# SparkFunVKeyVoltageKeypad.net
KiCad netlist of a schematic drawn in EAGLE
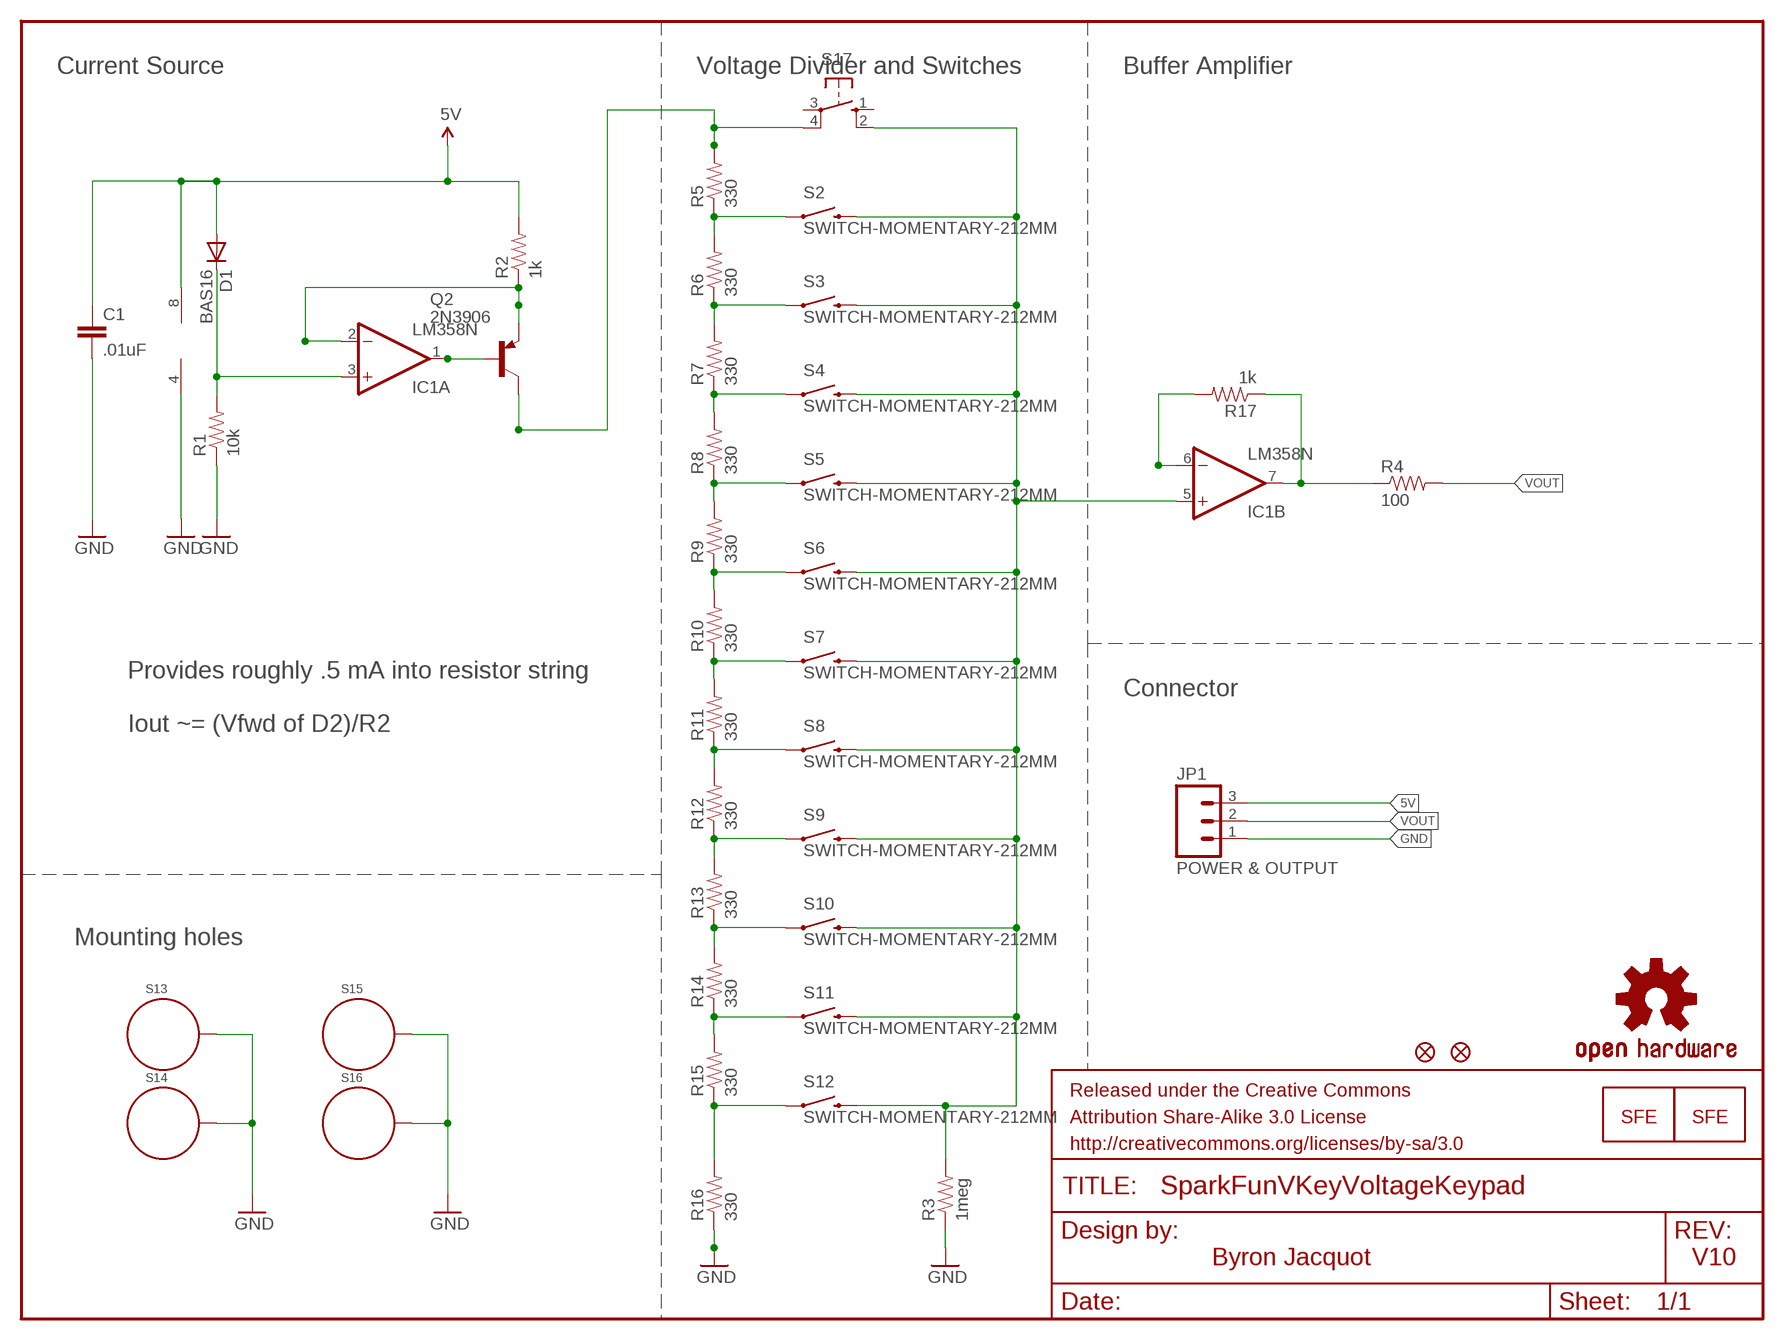
[diagram p0: schematic, sheet 1]

(export (version "E")
  (design (tool "Eeschema 10.0.6"))
  (components
    (comp (ref "C1")
      (value ".01uF")
      (footprint "eagle-import:0603-CAP")
      (libsource (lib "eagle-import") (part "10NF/10000PF-50V-10%(0603)"))
    )
    (comp (ref "D1")
      (value "BAS16")
      (footprint "eagle-import:SOD-323")
      (libsource (lib "eagle-import") (part "DIODESOD"))
    )
    (comp (ref "FID1")
      (value "FIDUCIALUFIDUCIAL")
      (footprint "eagle-import:MICRO-FIDUCIAL")
      (libsource (lib "eagle-import") (part "FIDUCIALUFIDUCIAL"))
    )
    (comp (ref "FID2")
      (value "FIDUCIALUFIDUCIAL")
      (footprint "eagle-import:MICRO-FIDUCIAL")
      (libsource (lib "eagle-import") (part "FIDUCIALUFIDUCIAL"))
    )
    (comp (ref "FRAME1")
      (value "FRAME-LETTER")
      (footprint "eagle-import:CREATIVE_COMMONS")
      (libsource (lib "eagle-import") (part "FRAME-LETTER"))
    )
    (comp (ref "IC1")
      (value "LM358N")
      (footprint "eagle-import:DIL08")
      (libsource (lib "eagle-import") (part "LM358N"))
    )
    (comp (ref "JP1")
      (value "POWER & OUTPUT")
      (footprint "eagle-import:1X03_NO_SILK")
      (libsource (lib "eagle-import") (part "M031X03_NO_SILK"))
    )
    (comp (ref "LOGO1")
      (value "LOGO-SFENEW")
      (footprint "eagle-import:SFE-NEW-WEBLOGO")
      (libsource (lib "eagle-import") (part "LOGO-SFENEW"))
    )
    (comp (ref "LOGO2")
      (value "LOGO-SFENEW")
      (footprint "eagle-import:SFE-NEW-WEBLOGO")
      (libsource (lib "eagle-import") (part "LOGO-SFENEW"))
    )
    (comp (ref "LOGO3")
      (value "OSHW-LOGOM")
      (footprint "eagle-import:OSHW-LOGO-M")
      (libsource (lib "eagle-import") (part "OSHW-LOGOM"))
    )
    (comp (ref "LOGO4")
      (value "OSHW-LOGOL")
      (footprint "eagle-import:OSHW-LOGO-L")
      (libsource (lib "eagle-import") (part "OSHW-LOGOL"))
    )
    (comp (ref "Q2")
      (value "2N3906")
      (footprint "eagle-import:TO92")
      (libsource (lib "eagle-import") (part "2N3906"))
    )
    (comp (ref "R1")
      (value "10k")
      (footprint "eagle-import:0603-RES")
      (libsource (lib "eagle-import") (part "10KOHM1/10W1%(0603)0603"))
    )
    (comp (ref "R2")
      (value "1k")
      (footprint "eagle-import:0603-RES")
      (libsource (lib "eagle-import") (part "1KOHM1/10W1%(0603)"))
    )
    (comp (ref "R3")
      (value "1meg")
      (footprint "eagle-import:0603-RES")
      (libsource (lib "eagle-import") (part "1M-1%"))
    )
    (comp (ref "R4")
      (value "100")
      (footprint "eagle-import:0603-RES")
      (libsource (lib "eagle-import") (part "100OHM1/10W1%(0603)"))
    )
    (comp (ref "R5")
      (value "330")
      (footprint "eagle-import:0603-RES")
      (libsource (lib "eagle-import") (part "330OHM1/10W1%(0603)"))
    )
    (comp (ref "R6")
      (value "330")
      (footprint "eagle-import:0603-RES")
      (fields (field (name "PROD_ID") "RES-00818"))
      (libsource (lib "eagle-import") (part "330OHM1/10W1%(0603)"))
    )
    (comp (ref "R7")
      (value "330")
      (footprint "eagle-import:0603-RES")
      (fields (field (name "PROD_ID") "RES-00818"))
      (libsource (lib "eagle-import") (part "330OHM1/10W1%(0603)"))
    )
    (comp (ref "R8")
      (value "330")
      (footprint "eagle-import:0603-RES")
      (fields (field (name "PROD_ID") "RES-00818"))
      (libsource (lib "eagle-import") (part "330OHM1/10W1%(0603)"))
    )
    (comp (ref "R9")
      (value "330")
      (footprint "eagle-import:0603-RES")
      (fields (field (name "PROD_ID") "RES-00818"))
      (libsource (lib "eagle-import") (part "330OHM1/10W1%(0603)"))
    )
    (comp (ref "R10")
      (value "330")
      (footprint "eagle-import:0603-RES")
      (fields (field (name "PROD_ID") "RES-00818"))
      (libsource (lib "eagle-import") (part "330OHM1/10W1%(0603)"))
    )
    (comp (ref "R11")
      (value "330")
      (footprint "eagle-import:0603-RES")
      (fields (field (name "PROD_ID") "RES-00818"))
      (libsource (lib "eagle-import") (part "330OHM1/10W1%(0603)"))
    )
    (comp (ref "R12")
      (value "330")
      (footprint "eagle-import:0603-RES")
      (fields (field (name "PROD_ID") "RES-00818"))
      (libsource (lib "eagle-import") (part "330OHM1/10W1%(0603)"))
    )
    (comp (ref "R13")
      (value "330")
      (footprint "eagle-import:0603-RES")
      (fields (field (name "PROD_ID") "RES-00818"))
      (libsource (lib "eagle-import") (part "330OHM1/10W1%(0603)"))
    )
    (comp (ref "R14")
      (value "330")
      (footprint "eagle-import:0603-RES")
      (fields (field (name "PROD_ID") "RES-00818"))
      (libsource (lib "eagle-import") (part "330OHM1/10W1%(0603)"))
    )
    (comp (ref "R15")
      (value "330")
      (footprint "eagle-import:0603-RES")
      (fields (field (name "PROD_ID") "RES-00818"))
      (libsource (lib "eagle-import") (part "330OHM1/10W1%(0603)"))
    )
    (comp (ref "R16")
      (value "330")
      (footprint "eagle-import:0603-RES")
      (fields (field (name "PROD_ID") "RES-00818"))
      (libsource (lib "eagle-import") (part "330OHM1/10W1%(0603)"))
    )
    (comp (ref "R17")
      (value "1k")
      (footprint "eagle-import:0603-RES")
      (libsource (lib "eagle-import") (part "1KOHM1/10W1%(0603)"))
    )
    (comp (ref "S2")
      (value "SWITCH-MOMENTARY-212MM")
      (footprint "eagle-import:TACTILE-PTH-12MM")
      (libsource (lib "eagle-import") (part "SWITCH-MOMENTARY-212MM"))
    )
    (comp (ref "S3")
      (value "SWITCH-MOMENTARY-212MM")
      (footprint "eagle-import:TACTILE-PTH-12MM")
      (libsource (lib "eagle-import") (part "SWITCH-MOMENTARY-212MM"))
    )
    (comp (ref "S4")
      (value "SWITCH-MOMENTARY-212MM")
      (footprint "eagle-import:TACTILE-PTH-12MM")
      (libsource (lib "eagle-import") (part "SWITCH-MOMENTARY-212MM"))
    )
    (comp (ref "S5")
      (value "SWITCH-MOMENTARY-212MM")
      (footprint "eagle-import:TACTILE-PTH-12MM")
      (libsource (lib "eagle-import") (part "SWITCH-MOMENTARY-212MM"))
    )
    (comp (ref "S6")
      (value "SWITCH-MOMENTARY-212MM")
      (footprint "eagle-import:TACTILE-PTH-12MM")
      (libsource (lib "eagle-import") (part "SWITCH-MOMENTARY-212MM"))
    )
    (comp (ref "S7")
      (value "SWITCH-MOMENTARY-212MM")
      (footprint "eagle-import:TACTILE-PTH-12MM")
      (libsource (lib "eagle-import") (part "SWITCH-MOMENTARY-212MM"))
    )
    (comp (ref "S8")
      (value "SWITCH-MOMENTARY-212MM")
      (footprint "eagle-import:TACTILE-PTH-12MM")
      (libsource (lib "eagle-import") (part "SWITCH-MOMENTARY-212MM"))
    )
    (comp (ref "S9")
      (value "SWITCH-MOMENTARY-212MM")
      (footprint "eagle-import:TACTILE-PTH-12MM")
      (libsource (lib "eagle-import") (part "SWITCH-MOMENTARY-212MM"))
    )
    (comp (ref "S10")
      (value "SWITCH-MOMENTARY-212MM")
      (footprint "eagle-import:TACTILE-PTH-12MM")
      (libsource (lib "eagle-import") (part "SWITCH-MOMENTARY-212MM"))
    )
    (comp (ref "S11")
      (value "SWITCH-MOMENTARY-212MM")
      (footprint "eagle-import:TACTILE-PTH-12MM")
      (libsource (lib "eagle-import") (part "SWITCH-MOMENTARY-212MM"))
    )
    (comp (ref "S12")
      (value "SWITCH-MOMENTARY-212MM")
      (footprint "eagle-import:TACTILE-PTH-12MM")
      (libsource (lib "eagle-import") (part "SWITCH-MOMENTARY-212MM"))
    )
    (comp (ref "S13")
      (value "STANDOFF_ELECTRICAL")
      (footprint "eagle-import:STANDOFF-ELECTRICAL")
      (libsource (lib "eagle-import") (part "STANDOFF_ELECTRICAL"))
    )
    (comp (ref "S14")
      (value "STANDOFF_ELECTRICAL")
      (footprint "eagle-import:STANDOFF-ELECTRICAL")
      (libsource (lib "eagle-import") (part "STANDOFF_ELECTRICAL"))
    )
    (comp (ref "S15")
      (value "STANDOFF_ELECTRICAL")
      (footprint "eagle-import:STANDOFF-ELECTRICAL")
      (libsource (lib "eagle-import") (part "STANDOFF_ELECTRICAL"))
    )
    (comp (ref "S16")
      (value "STANDOFF_ELECTRICAL")
      (footprint "eagle-import:STANDOFF-ELECTRICAL")
      (libsource (lib "eagle-import") (part "STANDOFF_ELECTRICAL"))
    )
    (comp (ref "S17")
      (value "10-XX")
      (footprint "eagle-import:B3F-10XX")
      (fields (field (name "MPN") "B3F-1000"))
      (libsource (lib "eagle-import") (part "10-XX"))
    )
  )
  (nets
    (net (code "1") (name "5V") (class "Default")
      (node (ref "C1") (pin "1") (pinfunction "1_1") (pintype "passive"))
      (node (ref "D1") (pin "2") (pinfunction "A_2") (pintype "passive"))
      (node (ref "IC1") (pin "8") (pinfunction "V+_8") (pintype "power_in"))
      (node (ref "JP1") (pin "3") (pinfunction "3_3") (pintype "passive"))
      (node (ref "R2") (pin "2") (pinfunction "2_2") (pintype "passive"))
    )
    (net (code "2") (name "GND") (class "Default")
      (node (ref "C1") (pin "2") (pinfunction "2_2") (pintype "passive"))
      (node (ref "IC1") (pin "4") (pinfunction "V-_4") (pintype "power_in"))
      (node (ref "JP1") (pin "1") (pinfunction "1_1") (pintype "passive"))
      (node (ref "R1") (pin "1") (pinfunction "1_1") (pintype "passive"))
      (node (ref "R16") (pin "1") (pinfunction "1_1") (pintype "passive"))
      (node (ref "R3") (pin "1") (pinfunction "1_1") (pintype "passive"))
      (node (ref "S13") (pin "P1") (pinfunction "P$1_P1") (pintype "bidirectional"))
      (node (ref "S14") (pin "P1") (pinfunction "P$1_P1") (pintype "bidirectional"))
      (node (ref "S15") (pin "P1") (pinfunction "P$1_P1") (pintype "bidirectional"))
      (node (ref "S16") (pin "P1") (pinfunction "P$1_P1") (pintype "bidirectional"))
    )
    (net (code "3") (name "Net-(D1-C)") (class "Default")
      (node (ref "D1") (pin "1") (pinfunction "C_1") (pintype "passive"))
      (node (ref "IC1") (pin "3") (pinfunction "+IN_3") (pintype "input"))
      (node (ref "R1") (pin "2") (pinfunction "2_2") (pintype "passive"))
    )
    (net (code "4") (name "Net-(IC1A--IN)") (class "Default")
      (node (ref "IC1") (pin "2") (pinfunction "-IN_2") (pintype "input"))
      (node (ref "Q2") (pin "3") (pinfunction "E_3") (pintype "passive"))
      (node (ref "R2") (pin "1") (pinfunction "1_1") (pintype "passive"))
    )
    (net (code "5") (name "Net-(IC1A-OUT)") (class "Default")
      (node (ref "IC1") (pin "1") (pinfunction "OUT_1") (pintype "output"))
      (node (ref "Q2") (pin "2") (pinfunction "B_2") (pintype "passive"))
    )
    (net (code "6") (name "Net-(IC1B-+IN)") (class "Default")
      (node (ref "IC1") (pin "5") (pinfunction "+IN_5") (pintype "input"))
      (node (ref "R3") (pin "2") (pinfunction "2_2") (pintype "passive"))
      (node (ref "S10") (pin "3") (pinfunction "2_3") (pintype "passive"))
      (node (ref "S11") (pin "3") (pinfunction "2_3") (pintype "passive"))
      (node (ref "S12") (pin "3") (pinfunction "2_3") (pintype "passive"))
      (node (ref "S17") (pin "2") (pinfunction "S1_2") (pintype "passive"))
      (node (ref "S2") (pin "3") (pinfunction "2_3") (pintype "passive"))
      (node (ref "S3") (pin "3") (pinfunction "2_3") (pintype "passive"))
      (node (ref "S4") (pin "3") (pinfunction "2_3") (pintype "passive"))
      (node (ref "S5") (pin "3") (pinfunction "2_3") (pintype "passive"))
      (node (ref "S6") (pin "3") (pinfunction "2_3") (pintype "passive"))
      (node (ref "S7") (pin "3") (pinfunction "2_3") (pintype "passive"))
      (node (ref "S8") (pin "3") (pinfunction "2_3") (pintype "passive"))
      (node (ref "S9") (pin "3") (pinfunction "2_3") (pintype "passive"))
    )
    (net (code "7") (name "Net-(IC1B--IN)") (class "Default")
      (node (ref "IC1") (pin "6") (pinfunction "-IN_6") (pintype "input"))
      (node (ref "R17") (pin "2") (pinfunction "2_2") (pintype "passive"))
    )
    (net (code "8") (name "Net-(IC1B-OUT)") (class "Default")
      (node (ref "IC1") (pin "7") (pinfunction "OUT_7") (pintype "output"))
      (node (ref "R17") (pin "1") (pinfunction "1_1") (pintype "passive"))
      (node (ref "R4") (pin "1") (pinfunction "1_1") (pintype "passive"))
    )
    (net (code "9") (name "Net-(Q2-C)") (class "Default")
      (node (ref "Q2") (pin "1") (pinfunction "C_1") (pintype "passive"))
      (node (ref "R5") (pin "2") (pinfunction "2_2") (pintype "passive"))
      (node (ref "S17") (pin "4") (pinfunction "P1_4") (pintype "passive"))
    )
    (net (code "10") (name "Net-(R5-Pad1)") (class "Default")
      (node (ref "R5") (pin "1") (pinfunction "1_1") (pintype "passive"))
      (node (ref "R6") (pin "2") (pinfunction "2_2") (pintype "passive"))
      (node (ref "S2") (pin "1") (pinfunction "1_1") (pintype "passive"))
    )
    (net (code "11") (name "Net-(R6-Pad1)") (class "Default")
      (node (ref "R6") (pin "1") (pinfunction "1_1") (pintype "passive"))
      (node (ref "R7") (pin "2") (pinfunction "2_2") (pintype "passive"))
      (node (ref "S3") (pin "1") (pinfunction "1_1") (pintype "passive"))
    )
    (net (code "12") (name "Net-(R7-Pad1)") (class "Default")
      (node (ref "R7") (pin "1") (pinfunction "1_1") (pintype "passive"))
      (node (ref "R8") (pin "2") (pinfunction "2_2") (pintype "passive"))
      (node (ref "S4") (pin "1") (pinfunction "1_1") (pintype "passive"))
    )
    (net (code "13") (name "Net-(R8-Pad1)") (class "Default")
      (node (ref "R8") (pin "1") (pinfunction "1_1") (pintype "passive"))
      (node (ref "R9") (pin "2") (pinfunction "2_2") (pintype "passive"))
      (node (ref "S5") (pin "1") (pinfunction "1_1") (pintype "passive"))
    )
    (net (code "14") (name "Net-(R10-Pad1)") (class "Default")
      (node (ref "R10") (pin "1") (pinfunction "1_1") (pintype "passive"))
      (node (ref "R11") (pin "2") (pinfunction "2_2") (pintype "passive"))
      (node (ref "S7") (pin "1") (pinfunction "1_1") (pintype "passive"))
    )
    (net (code "15") (name "Net-(R10-Pad2)") (class "Default")
      (node (ref "R10") (pin "2") (pinfunction "2_2") (pintype "passive"))
      (node (ref "R9") (pin "1") (pinfunction "1_1") (pintype "passive"))
      (node (ref "S6") (pin "1") (pinfunction "1_1") (pintype "passive"))
    )
    (net (code "16") (name "Net-(R11-Pad1)") (class "Default")
      (node (ref "R11") (pin "1") (pinfunction "1_1") (pintype "passive"))
      (node (ref "R12") (pin "2") (pinfunction "2_2") (pintype "passive"))
      (node (ref "S8") (pin "1") (pinfunction "1_1") (pintype "passive"))
    )
    (net (code "17") (name "Net-(R12-Pad1)") (class "Default")
      (node (ref "R12") (pin "1") (pinfunction "1_1") (pintype "passive"))
      (node (ref "R13") (pin "2") (pinfunction "2_2") (pintype "passive"))
      (node (ref "S9") (pin "1") (pinfunction "1_1") (pintype "passive"))
    )
    (net (code "18") (name "Net-(R13-Pad1)") (class "Default")
      (node (ref "R13") (pin "1") (pinfunction "1_1") (pintype "passive"))
      (node (ref "R14") (pin "2") (pinfunction "2_2") (pintype "passive"))
      (node (ref "S10") (pin "1") (pinfunction "1_1") (pintype "passive"))
    )
    (net (code "19") (name "Net-(R14-Pad1)") (class "Default")
      (node (ref "R14") (pin "1") (pinfunction "1_1") (pintype "passive"))
      (node (ref "R15") (pin "2") (pinfunction "2_2") (pintype "passive"))
      (node (ref "S11") (pin "1") (pinfunction "1_1") (pintype "passive"))
    )
    (net (code "20") (name "Net-(R15-Pad1)") (class "Default")
      (node (ref "R15") (pin "1") (pinfunction "1_1") (pintype "passive"))
      (node (ref "R16") (pin "2") (pinfunction "2_2") (pintype "passive"))
      (node (ref "S12") (pin "1") (pinfunction "1_1") (pintype "passive"))
    )
    (net (code "21") (name "VOUT") (class "Default")
      (node (ref "JP1") (pin "2") (pinfunction "2_2") (pintype "passive"))
      (node (ref "R4") (pin "2") (pinfunction "2_2") (pintype "passive"))
    )
    (net (code "22") (name "unconnected-(S17-P-Pad3)") (class "Default")
      (node (ref "S17") (pin "3") (pinfunction "P_3") (pintype "passive"))
    )
    (net (code "23") (name "unconnected-(S17-S-Pad1)") (class "Default")
      (node (ref "S17") (pin "1") (pinfunction "S_1") (pintype "passive"))
    )
  )
)
